# OneDigitSubcircuit.net
KiCad netlist of a schematic drawn in Altium Designer
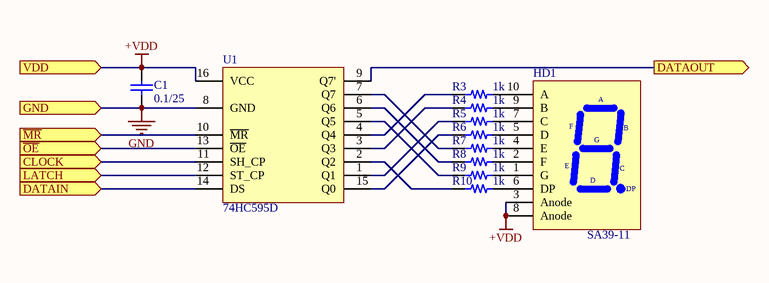
[diagram p0: OneDigitSubcircuit.SchDoc]

(export (version "E")
  (design (tool "Eeschema 10.0.6"))
  (components
    (comp (ref "C1")
      (value "0.1/25")
      (footprint "CAP0603")
      (description "Ceramic chip capacitor 0603")
      (fields
        (field (name "PARTNUMBER") "CAP0603")
        (field (name "VOLTAGE") "25")
        (field (name "AUTHOR") "oiezhov")
      )
      (libsource (lib "Library") (part "Capacitor"))
    )
    (comp (ref "HD1")
      (value "SA39-11")
      (footprint "39-11 7-segment")
      (description "9.9mm (0.39INCH) Single Digit 7-Segment Numeric Display (Common Anode)")
      (fields (field (name "AUTHOR") "oiezhov"))
      (libsource (lib "Library") (part "Single Digit 7-Segment (CA)"))
    )
    (comp (ref "R3")
      (value "1k")
      (footprint "RES0402")
      (description "Ceramic chip resistor")
      (fields (field (name "PARTNUMBER") "RES0402") (field (name "AUTHOR") "oiezhov"))
      (libsource (lib "Library") (part "Resistor"))
    )
    (comp (ref "R4")
      (value "1k")
      (footprint "RES0402")
      (description "Ceramic chip resistor")
      (fields (field (name "PARTNUMBER") "RES0402") (field (name "AUTHOR") "oiezhov"))
      (libsource (lib "Library") (part "Resistor"))
    )
    (comp (ref "R5")
      (value "1k")
      (footprint "RES0402")
      (description "Ceramic chip resistor")
      (fields (field (name "PARTNUMBER") "RES0402") (field (name "AUTHOR") "oiezhov"))
      (libsource (lib "Library") (part "Resistor"))
    )
    (comp (ref "R6")
      (value "1k")
      (footprint "RES0402")
      (description "Ceramic chip resistor")
      (fields (field (name "PARTNUMBER") "RES0402") (field (name "AUTHOR") "oiezhov"))
      (libsource (lib "Library") (part "Resistor"))
    )
    (comp (ref "R7")
      (value "1k")
      (footprint "RES0402")
      (description "Ceramic chip resistor")
      (fields (field (name "PARTNUMBER") "RES0402") (field (name "AUTHOR") "oiezhov"))
      (libsource (lib "Library") (part "Resistor"))
    )
    (comp (ref "R8")
      (value "1k")
      (footprint "RES0402")
      (description "Ceramic chip resistor")
      (fields (field (name "PARTNUMBER") "RES0402") (field (name "AUTHOR") "oiezhov"))
      (libsource (lib "Library") (part "Resistor"))
    )
    (comp (ref "R9")
      (value "1k")
      (footprint "RES0402")
      (description "Ceramic chip resistor")
      (fields (field (name "PARTNUMBER") "RES0402") (field (name "AUTHOR") "oiezhov"))
      (libsource (lib "Library") (part "Resistor"))
    )
    (comp (ref "R10")
      (value "1k")
      (footprint "RES0402")
      (description "Ceramic chip resistor")
      (fields (field (name "PARTNUMBER") "RES0402") (field (name "AUTHOR") "oiezhov"))
      (libsource (lib "Library") (part "Resistor"))
    )
    (comp (ref "U1")
      (value "74HC595D")
      (footprint "SO16")
      (description "8-bit serial-in, serial or parallel-out shift register with output latches; 3-state")
      (fields (field (name "AUTHOR") "oiezhov"))
      (libsource (lib "Library") (part "74595"))
    )
  )
  (nets
    (net (code "1") (name "+VDD") (class "Default")
      (node (ref "C1") (pin "2") (pinfunction "2_2") (pintype "passive"))
      (node (ref "HD1") (pin "3") (pinfunction "Anode_3") (pintype "passive"))
      (node (ref "HD1") (pin "8") (pinfunction "Anode_8") (pintype "passive"))
      (node (ref "U1") (pin "16") (pinfunction "VCC_16") (pintype "passive"))
    )
    (net (code "2") (name "/CLOCK") (class "Default")
      (node (ref "U1") (pin "11") (pinfunction "SH_CP_11") (pintype "passive"))
    )
    (net (code "3") (name "/DATAIN") (class "Default")
      (node (ref "U1") (pin "14") (pinfunction "DS_14") (pintype "passive"))
    )
    (net (code "4") (name "/DATAOUT") (class "Default")
      (node (ref "U1") (pin "9") (pinfunction "Q7'_9") (pintype "passive"))
    )
    (net (code "5") (name "/LATCH") (class "Default")
      (node (ref "U1") (pin "12") (pinfunction "ST_CP_12") (pintype "passive"))
    )
    (net (code "6") (name "/~{MR}") (class "Default")
      (node (ref "U1") (pin "10") (pinfunction "~{MR}_10") (pintype "passive"))
    )
    (net (code "7") (name "/~{OE}") (class "Default")
      (node (ref "U1") (pin "13") (pinfunction "~{OE}_13") (pintype "passive"))
    )
    (net (code "8") (name "GND") (class "Default")
      (node (ref "C1") (pin "1") (pinfunction "1_1") (pintype "passive"))
      (node (ref "U1") (pin "8") (pinfunction "GND_8") (pintype "passive"))
    )
    (net (code "9") (name "Net-(HD1-A)") (class "Default")
      (node (ref "HD1") (pin "10") (pinfunction "A_10") (pintype "passive"))
      (node (ref "R3") (pin "1") (pinfunction "1_1") (pintype "passive"))
    )
    (net (code "10") (name "Net-(HD1-B)") (class "Default")
      (node (ref "HD1") (pin "9") (pinfunction "B_9") (pintype "passive"))
      (node (ref "R4") (pin "1") (pinfunction "1_1") (pintype "passive"))
    )
    (net (code "11") (name "Net-(HD1-C)") (class "Default")
      (node (ref "HD1") (pin "7") (pinfunction "C_7") (pintype "passive"))
      (node (ref "R5") (pin "1") (pinfunction "1_1") (pintype "passive"))
    )
    (net (code "12") (name "Net-(HD1-D)") (class "Default")
      (node (ref "HD1") (pin "5") (pinfunction "D_5") (pintype "passive"))
      (node (ref "R6") (pin "1") (pinfunction "1_1") (pintype "passive"))
    )
    (net (code "13") (name "Net-(HD1-DP)") (class "Default")
      (node (ref "HD1") (pin "6") (pinfunction "DP_6") (pintype "passive"))
      (node (ref "R10") (pin "1") (pinfunction "1_1") (pintype "passive"))
    )
    (net (code "14") (name "Net-(HD1-E)") (class "Default")
      (node (ref "HD1") (pin "4") (pinfunction "E_4") (pintype "passive"))
      (node (ref "R7") (pin "1") (pinfunction "1_1") (pintype "passive"))
    )
    (net (code "15") (name "Net-(HD1-F)") (class "Default")
      (node (ref "HD1") (pin "2") (pinfunction "F_2") (pintype "passive"))
      (node (ref "R8") (pin "1") (pinfunction "1_1") (pintype "passive"))
    )
    (net (code "16") (name "Net-(HD1-G)") (class "Default")
      (node (ref "HD1") (pin "1") (pinfunction "G_1") (pintype "passive"))
      (node (ref "R9") (pin "1") (pinfunction "1_1") (pintype "passive"))
    )
    (net (code "17") (name "Net-(U1-Q0)") (class "Default")
      (node (ref "R6") (pin "2") (pinfunction "2_2") (pintype "passive"))
      (node (ref "U1") (pin "15") (pinfunction "Q0_15") (pintype "passive"))
    )
    (net (code "18") (name "Net-(U1-Q1)") (class "Default")
      (node (ref "R5") (pin "2") (pinfunction "2_2") (pintype "passive"))
      (node (ref "U1") (pin "1") (pinfunction "Q1_1") (pintype "passive"))
    )
    (net (code "19") (name "Net-(U1-Q2)") (class "Default")
      (node (ref "R10") (pin "2") (pinfunction "2_2") (pintype "passive"))
      (node (ref "U1") (pin "2") (pinfunction "Q2_2") (pintype "passive"))
    )
    (net (code "20") (name "Net-(U1-Q3)") (class "Default")
      (node (ref "R4") (pin "2") (pinfunction "2_2") (pintype "passive"))
      (node (ref "U1") (pin "3") (pinfunction "Q3_3") (pintype "passive"))
    )
    (net (code "21") (name "Net-(U1-Q4)") (class "Default")
      (node (ref "R3") (pin "2") (pinfunction "2_2") (pintype "passive"))
      (node (ref "U1") (pin "4") (pinfunction "Q4_4") (pintype "passive"))
    )
    (net (code "22") (name "Net-(U1-Q5)") (class "Default")
      (node (ref "R9") (pin "2") (pinfunction "2_2") (pintype "passive"))
      (node (ref "U1") (pin "5") (pinfunction "Q5_5") (pintype "passive"))
    )
    (net (code "23") (name "Net-(U1-Q6)") (class "Default")
      (node (ref "R8") (pin "2") (pinfunction "2_2") (pintype "passive"))
      (node (ref "U1") (pin "6") (pinfunction "Q6_6") (pintype "passive"))
    )
    (net (code "24") (name "Net-(U1-Q7)") (class "Default")
      (node (ref "R7") (pin "2") (pinfunction "2_2") (pintype "passive"))
      (node (ref "U1") (pin "7") (pinfunction "Q7_7") (pintype "passive"))
    )
  )
)
